# Uarts.net
KiCad netlist of a schematic drawn in Altium Designer
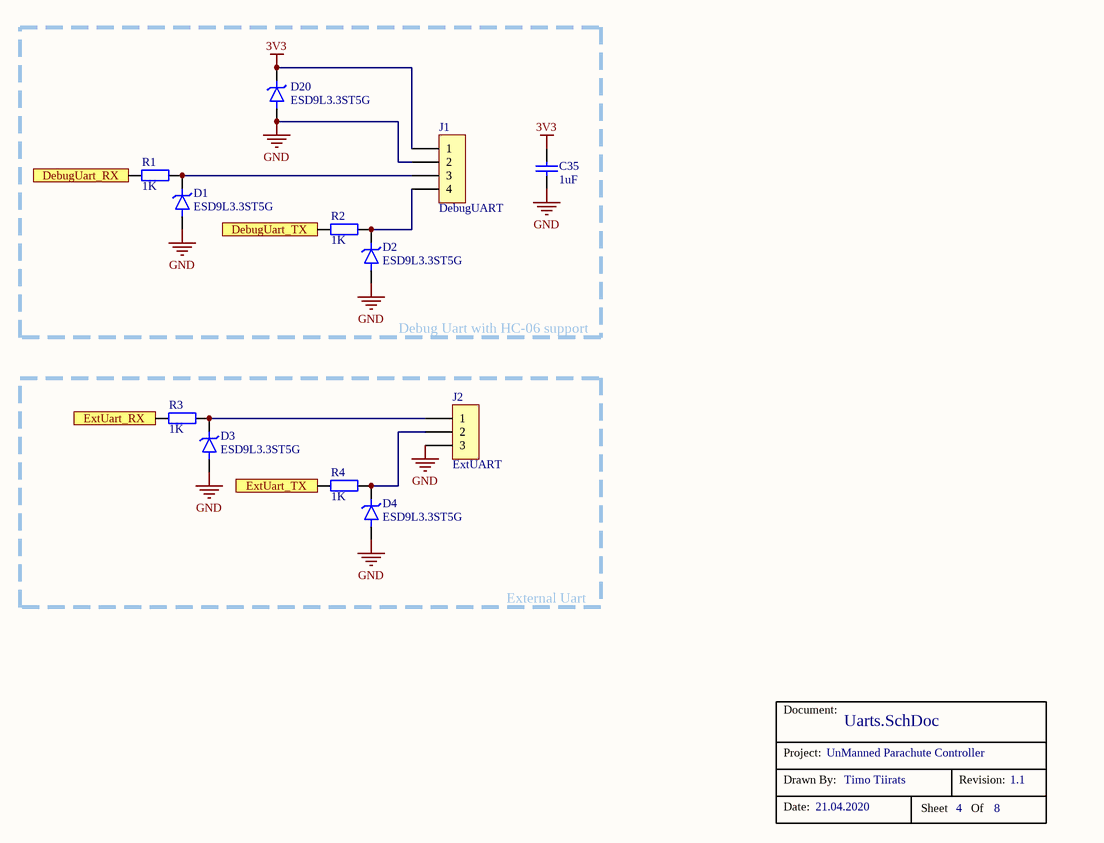
[diagram p0: Uarts.SchDoc]

(export (version "E")
  (design (tool "Eeschema 10.0.6"))
  (components
    (comp (ref "C35")
      (value "1uF*V")
      (footprint "C0603 N")
      (description "Ceramic capacitor")
      (fields (field (name "CAPACITANCE") "1uF"))
      (libsource (lib "Passives") (part "Capacitor"))
    )
    (comp (ref "D1")
      (value "ESD9L3.3ST5G")
      (footprint "SOD923F, NOMINAL")
      (description "TVS DIODE, Unidir, 3.3V/9V, 150mW, SOD-923, ESD9L3.3ST5G, ON SEMICONDUCTOR")
      (fields (field (name "MANUFACTURER") "ON Semiconductor"))
      (libsource (lib "Diodes") (part "ESD9L3.3ST5G"))
    )
    (comp (ref "D2")
      (value "ESD9L3.3ST5G")
      (footprint "SOD923F, NOMINAL")
      (description "TVS DIODE, Unidir, 3.3V/9V, 150mW, SOD-923, ESD9L3.3ST5G, ON SEMICONDUCTOR")
      (fields (field (name "MANUFACTURER") "ON Semiconductor"))
      (libsource (lib "Diodes") (part "ESD9L3.3ST5G"))
    )
    (comp (ref "D3")
      (value "ESD9L3.3ST5G")
      (footprint "SOD923F, NOMINAL")
      (description "TVS DIODE, Unidir, 3.3V/9V, 150mW, SOD-923, ESD9L3.3ST5G, ON SEMICONDUCTOR")
      (fields (field (name "MANUFACTURER") "ON Semiconductor"))
      (libsource (lib "Diodes") (part "ESD9L3.3ST5G"))
    )
    (comp (ref "D4")
      (value "ESD9L3.3ST5G")
      (footprint "SOD923F, NOMINAL")
      (description "TVS DIODE, Unidir, 3.3V/9V, 150mW, SOD-923, ESD9L3.3ST5G, ON SEMICONDUCTOR")
      (fields (field (name "MANUFACTURER") "ON Semiconductor"))
      (libsource (lib "Diodes") (part "ESD9L3.3ST5G"))
    )
    (comp (ref "D20")
      (value "ESD9L3.3ST5G")
      (footprint "SOD923F, NOMINAL")
      (description "TVS DIODE, Unidir, 3.3V/9V, 150mW, SOD-923, ESD9L3.3ST5G, ON SEMICONDUCTOR")
      (fields (field (name "MANUFACTURER") "ON Semiconductor"))
      (libsource (lib "Diodes") (part "ESD9L3.3ST5G"))
    )
    (comp (ref "J1")
      (value "DebugUART")
      (footprint "female 1x4 vertical")
      (libsource (lib "pinheader") (part "header 1x4 vertical"))
    )
    (comp (ref "J2")
      (value "ExtUART")
      (footprint "UART_HEADER")
      (libsource (lib "pinheader") (part "header 1x3 vertical"))
    )
    (comp (ref "R1")
      (value "1K")
      (footprint "R0603")
      (description "Resistor")
      (fields (field (name "RESISTANCE") "1K"))
      (libsource (lib "Passives") (part "Resistor"))
    )
    (comp (ref "R2")
      (value "1K")
      (footprint "R0603")
      (description "Resistor")
      (fields (field (name "RESISTANCE") "1K"))
      (libsource (lib "Passives") (part "Resistor"))
    )
    (comp (ref "R3")
      (value "1K")
      (footprint "R0603")
      (description "Resistor")
      (fields (field (name "RESISTANCE") "1K"))
      (libsource (lib "Passives") (part "Resistor"))
    )
    (comp (ref "R4")
      (value "1K")
      (footprint "R0603")
      (description "Resistor")
      (fields (field (name "RESISTANCE") "1K"))
      (libsource (lib "Passives") (part "Resistor"))
    )
  )
  (nets
    (net (code "1") (name "/DebugUart_RX") (class "Default")
      (node (ref "R1") (pin "2") (pinfunction "2_2") (pintype "passive"))
    )
    (net (code "2") (name "/DebugUart_TX") (class "Default")
      (node (ref "R2") (pin "2") (pinfunction "2_2") (pintype "passive"))
    )
    (net (code "3") (name "/ExtUart_RX") (class "Default")
      (node (ref "R3") (pin "2") (pinfunction "2_2") (pintype "passive"))
    )
    (net (code "4") (name "/ExtUart_TX") (class "Default")
      (node (ref "R4") (pin "2") (pinfunction "2_2") (pintype "passive"))
    )
    (net (code "5") (name "3V3") (class "Default")
      (node (ref "C35") (pin "2") (pinfunction "2_2") (pintype "passive"))
      (node (ref "D20") (pin "C") (pinfunction "C_C") (pintype "passive"))
      (node (ref "J1") (pin "1") (pinfunction "1_1") (pintype "passive"))
    )
    (net (code "6") (name "GND") (class "Default")
      (node (ref "C35") (pin "1") (pinfunction "1_1") (pintype "passive"))
      (node (ref "D1") (pin "A") (pinfunction "A_A") (pintype "passive"))
      (node (ref "D2") (pin "A") (pinfunction "A_A") (pintype "passive"))
      (node (ref "D20") (pin "A") (pinfunction "A_A") (pintype "passive"))
      (node (ref "D3") (pin "A") (pinfunction "A_A") (pintype "passive"))
      (node (ref "D4") (pin "A") (pinfunction "A_A") (pintype "passive"))
      (node (ref "J1") (pin "2") (pinfunction "2_2") (pintype "passive"))
      (node (ref "J2") (pin "3") (pinfunction "3_3") (pintype "passive"))
    )
    (net (code "7") (name "Net-(D1-PadC)") (class "Default")
      (node (ref "D1") (pin "C") (pinfunction "C_C") (pintype "passive"))
      (node (ref "J1") (pin "3") (pinfunction "3_3") (pintype "passive"))
      (node (ref "R1") (pin "1") (pinfunction "1_1") (pintype "passive"))
    )
    (net (code "8") (name "Net-(D2-PadC)") (class "Default")
      (node (ref "D2") (pin "C") (pinfunction "C_C") (pintype "passive"))
      (node (ref "J1") (pin "4") (pinfunction "4_4") (pintype "passive"))
      (node (ref "R2") (pin "1") (pinfunction "1_1") (pintype "passive"))
    )
    (net (code "9") (name "Net-(D3-PadC)") (class "Default")
      (node (ref "D3") (pin "C") (pinfunction "C_C") (pintype "passive"))
      (node (ref "J2") (pin "1") (pinfunction "1_1") (pintype "passive"))
      (node (ref "R3") (pin "1") (pinfunction "1_1") (pintype "passive"))
    )
    (net (code "10") (name "Net-(D4-PadC)") (class "Default")
      (node (ref "D4") (pin "C") (pinfunction "C_C") (pintype "passive"))
      (node (ref "J2") (pin "2") (pinfunction "2_2") (pintype "passive"))
      (node (ref "R4") (pin "1") (pinfunction "1_1") (pintype "passive"))
    )
  )
)
